# Nano_Wearable_Shield.net
KiCad netlist of a schematic drawn in EAGLE
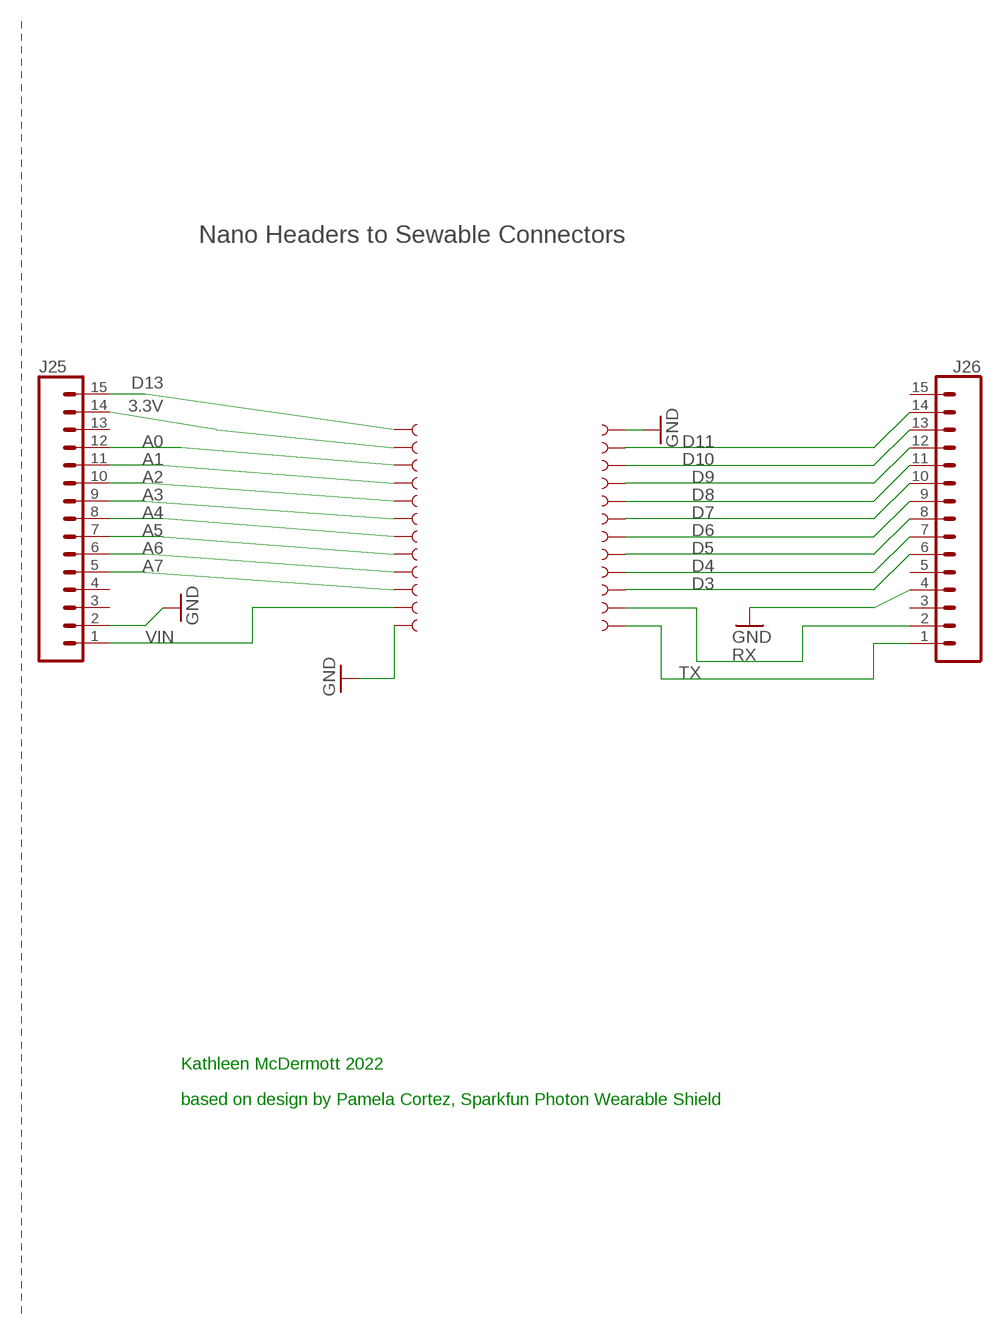
[diagram p0: schematic, sheet 1]

(export (version "E")
  (design (tool "Eeschema 10.0.6"))
  (components
    (comp (ref "J1")
      (value "PAD")
      (footprint "eagle-import:PAD-LONG-2-SIDED")
      (libsource (lib "eagle-import") (part "PAD"))
    )
    (comp (ref "J2")
      (value "PAD")
      (footprint "eagle-import:PAD-LONG-2-SIDED")
      (libsource (lib "eagle-import") (part "PAD"))
    )
    (comp (ref "J3")
      (value "PAD")
      (footprint "eagle-import:PAD-LONG-2-SIDED")
      (libsource (lib "eagle-import") (part "PAD"))
    )
    (comp (ref "J4")
      (value "PAD")
      (footprint "eagle-import:PAD-LONG-2-SIDED")
      (libsource (lib "eagle-import") (part "PAD"))
    )
    (comp (ref "J5")
      (value "PAD")
      (footprint "eagle-import:PAD-LONG-2-SIDED")
      (libsource (lib "eagle-import") (part "PAD"))
    )
    (comp (ref "J6")
      (value "PAD")
      (footprint "eagle-import:PAD-LONG-2-SIDED")
      (libsource (lib "eagle-import") (part "PAD"))
    )
    (comp (ref "J7")
      (value "PAD")
      (footprint "eagle-import:PAD-LONG-2-SIDED")
      (libsource (lib "eagle-import") (part "PAD"))
    )
    (comp (ref "J8")
      (value "PAD")
      (footprint "eagle-import:PAD-LONG-2-SIDED")
      (libsource (lib "eagle-import") (part "PAD"))
    )
    (comp (ref "J9")
      (value "PAD")
      (footprint "eagle-import:PAD-LONG-2-SIDED")
      (libsource (lib "eagle-import") (part "PAD"))
    )
    (comp (ref "J10")
      (value "PAD")
      (footprint "eagle-import:PAD-LONG-2-SIDED")
      (libsource (lib "eagle-import") (part "PAD"))
    )
    (comp (ref "J11")
      (value "PAD")
      (footprint "eagle-import:PAD-LONG-2-SIDED")
      (libsource (lib "eagle-import") (part "PAD"))
    )
    (comp (ref "J12")
      (value "PAD")
      (footprint "eagle-import:PAD-LONG-2-SIDED")
      (libsource (lib "eagle-import") (part "PAD"))
    )
    (comp (ref "J13")
      (value "PAD")
      (footprint "eagle-import:PAD-LONG-2-SIDED")
      (libsource (lib "eagle-import") (part "PAD"))
    )
    (comp (ref "J14")
      (value "PAD")
      (footprint "eagle-import:PAD-LONG-2-SIDED")
      (libsource (lib "eagle-import") (part "PAD"))
    )
    (comp (ref "J15")
      (value "PAD")
      (footprint "eagle-import:PAD-LONG-2-SIDED")
      (libsource (lib "eagle-import") (part "PAD"))
    )
    (comp (ref "J16")
      (value "PAD")
      (footprint "eagle-import:PAD-LONG-2-SIDED")
      (libsource (lib "eagle-import") (part "PAD"))
    )
    (comp (ref "J17")
      (value "PAD")
      (footprint "eagle-import:PAD-LONG-2-SIDED")
      (libsource (lib "eagle-import") (part "PAD"))
    )
    (comp (ref "J18")
      (value "PAD")
      (footprint "eagle-import:PAD-LONG-2-SIDED")
      (libsource (lib "eagle-import") (part "PAD"))
    )
    (comp (ref "J19")
      (value "PAD")
      (footprint "eagle-import:PAD-LONG-2-SIDED")
      (libsource (lib "eagle-import") (part "PAD"))
    )
    (comp (ref "J20")
      (value "PAD")
      (footprint "eagle-import:PAD-LONG-2-SIDED")
      (libsource (lib "eagle-import") (part "PAD"))
    )
    (comp (ref "J21")
      (value "PAD")
      (footprint "eagle-import:PAD-LONG-2-SIDED")
      (libsource (lib "eagle-import") (part "PAD"))
    )
    (comp (ref "J22")
      (value "PAD")
      (footprint "eagle-import:PAD-LONG-2-SIDED")
      (libsource (lib "eagle-import") (part "PAD"))
    )
    (comp (ref "J23")
      (value "PAD")
      (footprint "eagle-import:PAD-LONG-2-SIDED")
      (libsource (lib "eagle-import") (part "PAD"))
    )
    (comp (ref "J24")
      (value "PAD")
      (footprint "eagle-import:PAD-LONG-2-SIDED")
      (libsource (lib "eagle-import") (part "PAD"))
    )
    (comp (ref "J25")
      (value "CONN_15")
      (footprint "eagle-import:1X15")
      (libsource (lib "eagle-import") (part "CONN_15"))
    )
    (comp (ref "J26")
      (value "CONN_15")
      (footprint "eagle-import:1X15")
      (libsource (lib "eagle-import") (part "CONN_15"))
    )
  )
  (nets
    (net (code "1") (name "/3.3V") (class "Default")
      (node (ref "J2") (pin "1") (pinfunction "1_1") (pintype "bidirectional"))
      (node (ref "J25") (pin "14") (pinfunction "14_14") (pintype "passive"))
    )
    (net (code "2") (name "/A0") (class "Default")
      (node (ref "J25") (pin "12") (pinfunction "12_12") (pintype "passive"))
      (node (ref "J3") (pin "1") (pinfunction "1_1") (pintype "bidirectional"))
    )
    (net (code "3") (name "/A1") (class "Default")
      (node (ref "J25") (pin "11") (pinfunction "11_11") (pintype "passive"))
      (node (ref "J4") (pin "1") (pinfunction "1_1") (pintype "bidirectional"))
    )
    (net (code "4") (name "/A2") (class "Default")
      (node (ref "J25") (pin "10") (pinfunction "10_10") (pintype "passive"))
      (node (ref "J5") (pin "1") (pinfunction "1_1") (pintype "bidirectional"))
    )
    (net (code "5") (name "/A3") (class "Default")
      (node (ref "J25") (pin "9") (pinfunction "9_9") (pintype "passive"))
      (node (ref "J6") (pin "1") (pinfunction "1_1") (pintype "bidirectional"))
    )
    (net (code "6") (name "/A4") (class "Default")
      (node (ref "J25") (pin "8") (pinfunction "8_8") (pintype "passive"))
      (node (ref "J7") (pin "1") (pinfunction "1_1") (pintype "bidirectional"))
    )
    (net (code "7") (name "/A5") (class "Default")
      (node (ref "J25") (pin "7") (pinfunction "7_7") (pintype "passive"))
      (node (ref "J8") (pin "1") (pinfunction "1_1") (pintype "bidirectional"))
    )
    (net (code "8") (name "/A6") (class "Default")
      (node (ref "J25") (pin "6") (pinfunction "6_6") (pintype "passive"))
      (node (ref "J9") (pin "1") (pinfunction "1_1") (pintype "bidirectional"))
    )
    (net (code "9") (name "/A7") (class "Default")
      (node (ref "J10") (pin "1") (pinfunction "1_1") (pintype "bidirectional"))
      (node (ref "J25") (pin "5") (pinfunction "5_5") (pintype "passive"))
    )
    (net (code "10") (name "/D3") (class "Default")
      (node (ref "J22") (pin "1") (pinfunction "1_1") (pintype "bidirectional"))
      (node (ref "J26") (pin "6") (pinfunction "6_6") (pintype "passive"))
    )
    (net (code "11") (name "/D4") (class "Default")
      (node (ref "J21") (pin "1") (pinfunction "1_1") (pintype "bidirectional"))
      (node (ref "J26") (pin "7") (pinfunction "7_7") (pintype "passive"))
    )
    (net (code "12") (name "/D5") (class "Default")
      (node (ref "J20") (pin "1") (pinfunction "1_1") (pintype "bidirectional"))
      (node (ref "J26") (pin "8") (pinfunction "8_8") (pintype "passive"))
    )
    (net (code "13") (name "/D6") (class "Default")
      (node (ref "J19") (pin "1") (pinfunction "1_1") (pintype "bidirectional"))
      (node (ref "J26") (pin "9") (pinfunction "9_9") (pintype "passive"))
    )
    (net (code "14") (name "/D7") (class "Default")
      (node (ref "J18") (pin "1") (pinfunction "1_1") (pintype "bidirectional"))
      (node (ref "J26") (pin "10") (pinfunction "10_10") (pintype "passive"))
    )
    (net (code "15") (name "/D8") (class "Default")
      (node (ref "J17") (pin "1") (pinfunction "1_1") (pintype "bidirectional"))
      (node (ref "J26") (pin "11") (pinfunction "11_11") (pintype "passive"))
    )
    (net (code "16") (name "/D9") (class "Default")
      (node (ref "J16") (pin "1") (pinfunction "1_1") (pintype "bidirectional"))
      (node (ref "J26") (pin "12") (pinfunction "12_12") (pintype "passive"))
    )
    (net (code "17") (name "/D10") (class "Default")
      (node (ref "J15") (pin "1") (pinfunction "1_1") (pintype "bidirectional"))
      (node (ref "J26") (pin "13") (pinfunction "13_13") (pintype "passive"))
    )
    (net (code "18") (name "/D11") (class "Default")
      (node (ref "J14") (pin "1") (pinfunction "1_1") (pintype "bidirectional"))
      (node (ref "J26") (pin "14") (pinfunction "14_14") (pintype "passive"))
    )
    (net (code "19") (name "/D13") (class "Default")
      (node (ref "J1") (pin "1") (pinfunction "1_1") (pintype "bidirectional"))
      (node (ref "J25") (pin "15") (pinfunction "15_15") (pintype "passive"))
    )
    (net (code "20") (name "/RX") (class "Default")
      (node (ref "J23") (pin "1") (pinfunction "1_1") (pintype "bidirectional"))
      (node (ref "J26") (pin "2") (pinfunction "2_2") (pintype "passive"))
    )
    (net (code "21") (name "/TX") (class "Default")
      (node (ref "J24") (pin "1") (pinfunction "1_1") (pintype "bidirectional"))
      (node (ref "J26") (pin "1") (pinfunction "1_1") (pintype "passive"))
    )
    (net (code "22") (name "/VIN") (class "Default")
      (node (ref "J11") (pin "1") (pinfunction "1_1") (pintype "bidirectional"))
      (node (ref "J25") (pin "1") (pinfunction "1_1") (pintype "passive"))
    )
    (net (code "23") (name "GND") (class "Default")
      (node (ref "J12") (pin "1") (pinfunction "1_1") (pintype "bidirectional"))
      (node (ref "J13") (pin "1") (pinfunction "1_1") (pintype "bidirectional"))
      (node (ref "J25") (pin "2") (pinfunction "2_2") (pintype "passive"))
      (node (ref "J26") (pin "4") (pinfunction "4_4") (pintype "passive"))
    )
    (net (code "24") (name "unconnected-(J25-Pad3)") (class "Default")
      (node (ref "J25") (pin "3") (pinfunction "3_3") (pintype "passive"))
    )
    (net (code "25") (name "unconnected-(J25-Pad4)") (class "Default")
      (node (ref "J25") (pin "4") (pinfunction "4_4") (pintype "passive"))
    )
    (net (code "26") (name "unconnected-(J25-Pad13)") (class "Default")
      (node (ref "J25") (pin "13") (pinfunction "13_13") (pintype "passive"))
    )
    (net (code "27") (name "unconnected-(J26-Pad3)") (class "Default")
      (node (ref "J26") (pin "3") (pinfunction "3_3") (pintype "passive"))
    )
    (net (code "28") (name "unconnected-(J26-Pad5)") (class "Default")
      (node (ref "J26") (pin "5") (pinfunction "5_5") (pintype "passive"))
    )
    (net (code "29") (name "unconnected-(J26-Pad15)") (class "Default")
      (node (ref "J26") (pin "15") (pinfunction "15_15") (pintype "passive"))
    )
  )
)
